# ISL6236A_PS.net
KiCad netlist of a schematic drawn in Altium Designer
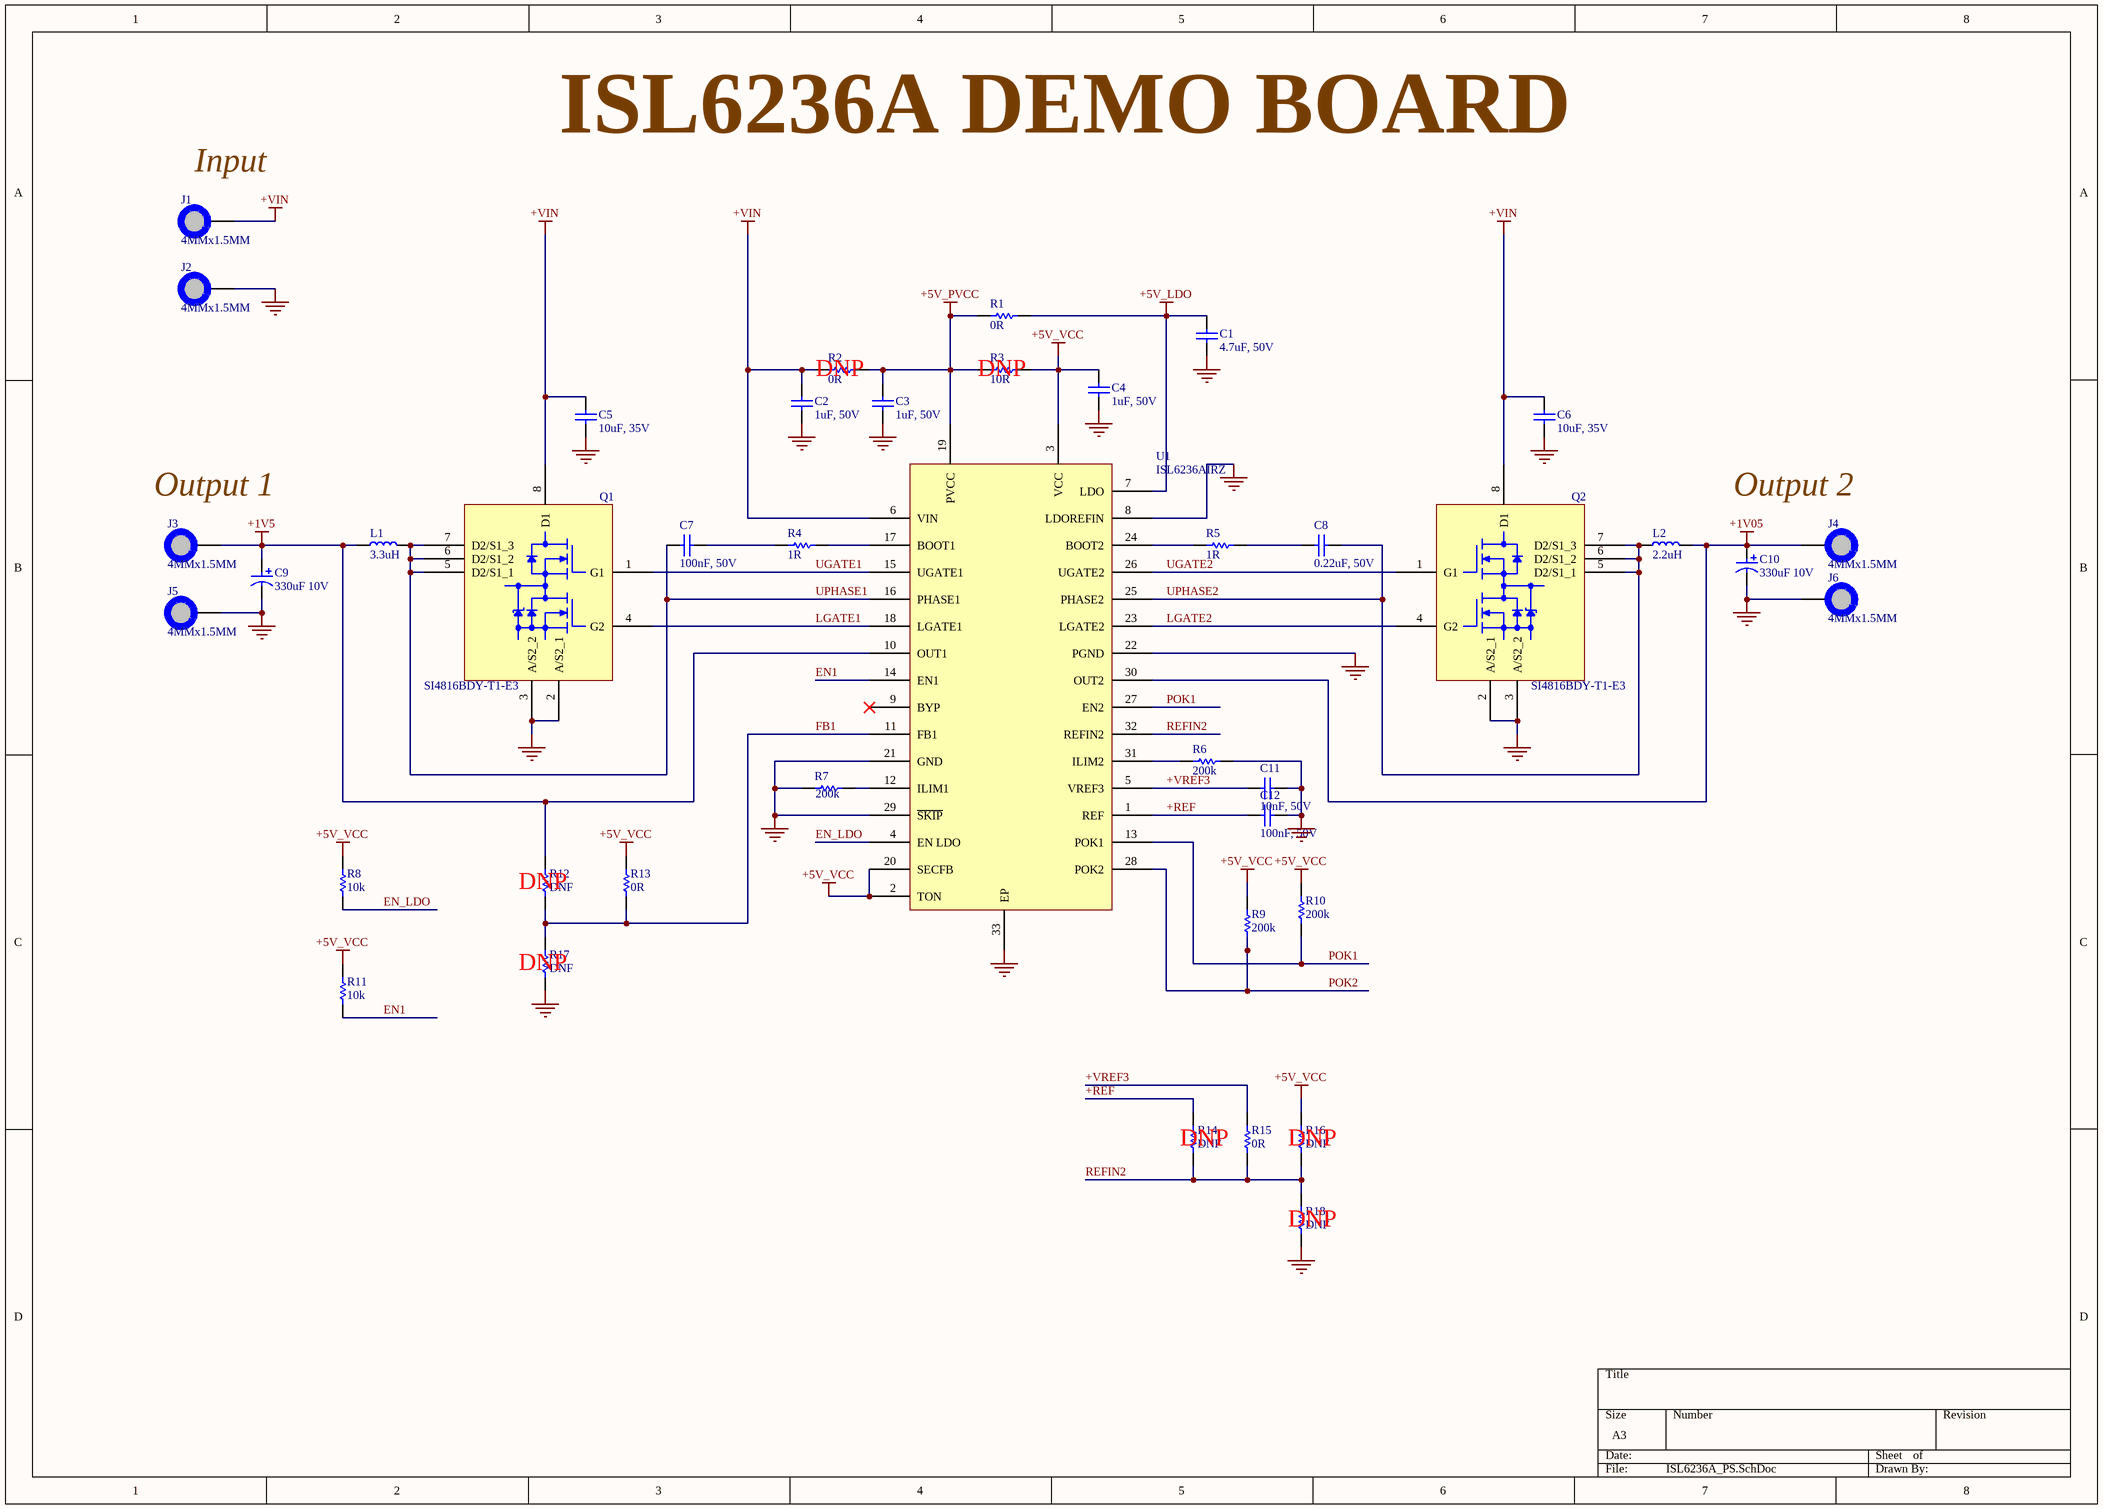
[diagram p0: ISL6236A_PS.SchDoc]

(export (version "E")
  (design (tool "Eeschema 10.0.6"))
  (components
    (comp (ref "C1")
      (value "4.7uF, 50V")
      (footprint "CAP1206")
      (description "CAP CER 4.7UF 50V X5R 1206")
      (fields
        (field (name "MANUFACTURER") "TDK")
        (field (name "MANUFACTURER PART NUMBER") "C3216X5R1H475K160AB")
      )
      (libsource (lib "ISL6236A_PS") (part "C3216X5R1H475K160AB"))
    )
    (comp (ref "C2")
      (value "1uF, 50V")
      (footprint "Cap0805")
      (description "CAP CER SMD/SMT 1uF 50 Volts 10% X7R")
      (fields
        (field (name "MANUFACTURER") "KEMET")
        (field (name "MANUFACTURER PART NUMBER") "C0805C105K5RACTU")
      )
      (libsource (lib "ISL6236A_PS") (part "C0805C105K5RACTU"))
    )
    (comp (ref "C3")
      (value "1uF, 50V")
      (footprint "Cap0805")
      (description "CAP CER SMD/SMT 1uF 50 Volts 10% X7R")
      (fields
        (field (name "MANUFACTURER") "KEMET")
        (field (name "MANUFACTURER PART NUMBER") "C0805C105K5RACTU")
      )
      (libsource (lib "ISL6236A_PS") (part "C0805C105K5RACTU"))
    )
    (comp (ref "C4")
      (value "1uF, 50V")
      (footprint "Cap0805")
      (description "CAP CER SMD/SMT 1uF 50 Volts 10% X7R")
      (fields
        (field (name "MANUFACTURER") "KEMET")
        (field (name "MANUFACTURER PART NUMBER") "C0805C105K5RACTU")
      )
      (libsource (lib "ISL6236A_PS") (part "C0805C105K5RACTU"))
    )
    (comp (ref "C5")
      (value "10uF, 35V")
      (footprint "CAP 1210")
      (description "CAP CER 10UF 35V X5R 1210")
      (fields
        (field (name "MANUFACTURER") "KEMET")
        (field (name "MANUFACTURER PART NUMBER") "C1210C106K6PACTU")
      )
      (libsource (lib "ISL6236A_PS") (part "C1210C106K6PACTU"))
    )
    (comp (ref "C6")
      (value "10uF, 35V")
      (footprint "CAP 1210")
      (description "CAP CER 10UF 35V X5R 1210")
      (fields
        (field (name "MANUFACTURER") "KEMET")
        (field (name "MANUFACTURER PART NUMBER") "C1210C106K6PACTU")
      )
      (libsource (lib "ISL6236A_PS") (part "C1210C106K6PACTU"))
    )
    (comp (ref "C7")
      (value "100nF, 50V")
      (footprint "Cap0805")
      (description "CAP CER 100nF; 50VDC; X7R; ±10%; SMD; 0805")
      (fields
        (field (name "MANUFACTURER") "KEMET")
        (field (name "MANUFACTURER PART NUMBER") "C0805C104K5RACTU")
      )
      (libsource (lib "ISL6236A_PS") (part "C0805C104K5RACTU"))
    )
    (comp (ref "C8")
      (value "0.22uF, 50V")
      (footprint "Cap0805")
      (description "CAP CER 0.22UF 50V X7R 0805")
      (fields
        (field (name "MANUFACTURER") "KEMET")
        (field (name "MANUFACTURER PART NUMBER") "C0805C224K5RACTU")
      )
      (libsource (lib "ISL6236A_PS") (part "C0805C224K5RACTU"))
    )
    (comp (ref "C9")
      (value "330uF 10V")
      (footprint "CAP 7343-43")
      (description "Tantalum Capacitors - Polymer SMD 330uF 10volts 20%")
      (fields
        (field (name "MANUFACTURER") "KEMET")
        (field (name "MANUFACTURER PART NUMBER") "T530X337M010ATE004")
      )
      (libsource (lib "ISL6236A_PS") (part "T530X337M010ATE004"))
    )
    (comp (ref "C10")
      (value "330uF 10V")
      (footprint "CAP 7343-43")
      (description "Tantalum Capacitors - Polymer SMD 330uF 10volts 20%")
      (fields
        (field (name "MANUFACTURER") "KEMET")
        (field (name "MANUFACTURER PART NUMBER") "T530X337M010ATE004")
      )
      (libsource (lib "ISL6236A_PS") (part "T530X337M010ATE004"))
    )
    (comp (ref "C11")
      (value "10nF, 50V")
      (footprint "Cap0805")
      (description "CAP CER 10000PF 50V X7R 0805")
      (fields
        (field (name "MANUFACTURER") "KEMET")
        (field (name "MANUFACTURER PART NUMBER") "C0805F103K5RACTU")
      )
      (libsource (lib "ISL6236A_PS") (part "C0805F103K5RACTU"))
    )
    (comp (ref "C12")
      (value "100nF, 50V")
      (footprint "Cap0805")
      (description "CAP CER 100nF; 50VDC; X7R; ±10%; SMD; 0805")
      (fields
        (field (name "MANUFACTURER") "KEMET")
        (field (name "MANUFACTURER PART NUMBER") "C0805C104K5RACTU")
      )
      (libsource (lib "ISL6236A_PS") (part "C0805C104K5RACTU"))
    )
    (comp (ref "J1")
      (value "4MMx1.5MM")
      (footprint "PAD_WITH_HOLE_4MMx1MM5")
      (description "PAd with a hole 4mm x 1.5mm")
      (libsource (lib "ISL6236A_PS") (part "PAD_WITH_HOLE_4MMx1MM5"))
    )
    (comp (ref "J2")
      (value "4MMx1.5MM")
      (footprint "PAD_WITH_HOLE_4MMx1MM5")
      (description "PAd with a hole 4mm x 1.5mm")
      (libsource (lib "ISL6236A_PS") (part "PAD_WITH_HOLE_4MMx1MM5"))
    )
    (comp (ref "J3")
      (value "4MMx1.5MM")
      (footprint "PAD_WITH_HOLE_4MMx1MM5")
      (description "PAd with a hole 4mm x 1.5mm")
      (libsource (lib "ISL6236A_PS") (part "PAD_WITH_HOLE_4MMx1MM5"))
    )
    (comp (ref "J4")
      (value "4MMx1.5MM")
      (footprint "PAD_WITH_HOLE_4MMx1MM5")
      (description "PAd with a hole 4mm x 1.5mm")
      (libsource (lib "ISL6236A_PS") (part "PAD_WITH_HOLE_4MMx1MM5"))
    )
    (comp (ref "J5")
      (value "4MMx1.5MM")
      (footprint "PAD_WITH_HOLE_4MMx1MM5")
      (description "PAd with a hole 4mm x 1.5mm")
      (libsource (lib "ISL6236A_PS") (part "PAD_WITH_HOLE_4MMx1MM5"))
    )
    (comp (ref "J6")
      (value "4MMx1.5MM")
      (footprint "PAD_WITH_HOLE_4MMx1MM5")
      (description "PAd with a hole 4mm x 1.5mm")
      (libsource (lib "ISL6236A_PS") (part "PAD_WITH_HOLE_4MMx1MM5"))
    )
    (comp (ref "L1")
      (value "3.3uH")
      (footprint "IND_DR125")
      (description "FIXED IND 3.3UH 12.7A 6.3 MOHM")
      (fields
        (field (name "MANUFACTURER") "Eaton Coiltronics")
        (field (name "MANUFACTURER PART NUMBER") "DR125-3R3-R")
      )
      (libsource (lib "ISL6236A_PS") (part "DR125-3R3-R"))
    )
    (comp (ref "L2")
      (value "2.2uH")
      (footprint "IND_DR125")
      (description "FIXED IND 2.2UH 10.9A 4.5 MOHM")
      (fields
        (field (name "MANUFACTURER") "Eaton Cooper")
        (field (name "MANUFACTURER PART NUMBER") "DR125-2R2-R")
      )
      (libsource (lib "ISL6236A_PS") (part "DR125-2R2-R"))
    )
    (comp (ref "Q1")
      (value "SI4816BDY-T1-E3")
      (footprint "SOP8")
      (description "MOSFET 2N-CH 30V 5.8A 8-SOIC")
      (fields (field (name "MANUFACTURER") "Vishay Siliconix"))
      (libsource (lib "ISL6236A_PS") (part "SI4816BDY-T1-E3"))
    )
    (comp (ref "Q2")
      (value "SI4816BDY-T1-E3")
      (footprint "SOP8")
      (description "MOSFET 2N-CH 30V 5.8A 8-SOIC")
      (fields (field (name "MANUFACTURER") "Vishay Siliconix"))
      (libsource (lib "") (part "SI4816BDY-T1-E3_1"))
    )
    (comp (ref "R1")
      (value "0R")
      (footprint "RES0805")
      (description "Thick Film Resistors - SMD 1/8W 0.0ohm 5%")
      (fields
        (field (name "MANUFACTURER") "Yageo")
        (field (name "MANUFACTURER PART NUMBER") "AC0805JR-070RL")
      )
      (libsource (lib "ISL6236A_PS") (part "AC0805JR-070RL"))
    )
    (comp (ref "R2")
      (value "0R")
      (footprint "RES0805")
      (description "Thick Film Resistors - SMD 1/8W 0.0ohm 5%")
      (fields
        (field (name "MANUFACTURER") "Yageo")
        (field (name "MANUFACTURER PART NUMBER") "AC0805JR-070RL")
      )
      (libsource (lib "ISL6236A_PS") (part "AC0805JR-070RL"))
    )
    (comp (ref "R3")
      (value "10R")
      (footprint "RES0805")
      (description "Thick Film Resistors - SMD 1/8W 10ohm 1% AEC-Q200")
      (fields
        (field (name "MANUFACTURER") "Yageo")
        (field (name "MANUFACTURER PART NUMBER") "AC0805FR-0710RL")
      )
      (libsource (lib "ISL6236A_PS") (part "AC0805FR-0710RL"))
    )
    (comp (ref "R4")
      (value "1R")
      (footprint "RES0805")
      (description "AC Series 0805 0.125 W 1 Ohm ±1% ±200 ppm/°C SMT Thick Film Chip Resistor")
      (fields
        (field (name "MANUFACTURER") "Yageo")
        (field (name "MANUFACTURER PART NUMBER") "AC0805FR-071RL")
      )
      (libsource (lib "ISL6236A_PS") (part "AC0805FR-071RL"))
    )
    (comp (ref "R5")
      (value "1R")
      (footprint "RES0805")
      (description "AC Series 0805 0.125 W 1 Ohm ±1% ±200 ppm/°C SMT Thick Film Chip Resistor")
      (fields
        (field (name "MANUFACTURER") "Yageo")
        (field (name "MANUFACTURER PART NUMBER") "AC0805FR-071RL")
      )
      (libsource (lib "ISL6236A_PS") (part "AC0805FR-071RL"))
    )
    (comp (ref "R6")
      (value "200k")
      (footprint "RES0805")
      (description "Thick Film Resistors - SMD 1/8W 200K ohm 1% AEC-Q200")
      (fields
        (field (name "MANUFACTURER") "Yageo")
        (field (name "MANUFACTURER PART NUMBER") "AC0805FR-07200KL")
      )
      (libsource (lib "ISL6236A_PS") (part "AC0805FR-07200KL"))
    )
    (comp (ref "R7")
      (value "200k")
      (footprint "RES0805")
      (description "Thick Film Resistors - SMD 1/8W 200K ohm 1% AEC-Q200")
      (fields
        (field (name "MANUFACTURER") "Yageo")
        (field (name "MANUFACTURER PART NUMBER") "AC0805FR-07200KL")
      )
      (libsource (lib "ISL6236A_PS") (part "AC0805FR-07200KL"))
    )
    (comp (ref "R8")
      (value "10k")
      (footprint "RES0805")
      (description "RES SMD 10K OHM 1% 1/8W 0805")
      (fields
        (field (name "MANUFACTURER") "Yageo")
        (field (name "MANUFACTURER PART NUMBER") "AC0805FR-0710KL")
      )
      (libsource (lib "ISL6236A_PS") (part "AC0805FR-0710KL"))
    )
    (comp (ref "R9")
      (value "200k")
      (footprint "RES0805")
      (description "Thick Film Resistors - SMD 1/8W 200K ohm 1% AEC-Q200")
      (fields
        (field (name "MANUFACTURER") "Yageo")
        (field (name "MANUFACTURER PART NUMBER") "AC0805FR-07200KL")
      )
      (libsource (lib "ISL6236A_PS") (part "AC0805FR-07200KL"))
    )
    (comp (ref "R10")
      (value "200k")
      (footprint "RES0805")
      (description "Thick Film Resistors - SMD 1/8W 200K ohm 1% AEC-Q200")
      (fields
        (field (name "MANUFACTURER") "Yageo")
        (field (name "MANUFACTURER PART NUMBER") "AC0805FR-07200KL")
      )
      (libsource (lib "ISL6236A_PS") (part "AC0805FR-07200KL"))
    )
    (comp (ref "R11")
      (value "10k")
      (footprint "RES0805")
      (description "RES SMD 10K OHM 1% 1/8W 0805")
      (fields
        (field (name "MANUFACTURER") "Yageo")
        (field (name "MANUFACTURER PART NUMBER") "AC0805FR-0710KL")
      )
      (libsource (lib "ISL6236A_PS") (part "AC0805FR-0710KL"))
    )
    (comp (ref "R12")
      (value "DNF")
      (footprint "RES0805")
      (description "RES General")
      (libsource (lib "ISL6236A_PS") (part "RES General"))
    )
    (comp (ref "R13")
      (value "0R")
      (footprint "RES0805")
      (description "Thick Film Resistors - SMD 1/8W 0.0ohm 5%")
      (fields
        (field (name "MANUFACTURER") "Yageo")
        (field (name "MANUFACTURER PART NUMBER") "AC0805JR-070RL")
      )
      (libsource (lib "ISL6236A_PS") (part "AC0805JR-070RL"))
    )
    (comp (ref "R14")
      (value "DNF")
      (footprint "RES0805")
      (description "RES General")
      (libsource (lib "ISL6236A_PS") (part "RES General"))
    )
    (comp (ref "R15")
      (value "0R")
      (footprint "RES0805")
      (description "Thick Film Resistors - SMD 1/8W 0.0ohm 5%")
      (fields
        (field (name "MANUFACTURER") "Yageo")
        (field (name "MANUFACTURER PART NUMBER") "AC0805JR-070RL")
      )
      (libsource (lib "ISL6236A_PS") (part "AC0805JR-070RL"))
    )
    (comp (ref "R16")
      (value "DNF")
      (footprint "RES0805")
      (description "RES General")
      (libsource (lib "ISL6236A_PS") (part "RES General"))
    )
    (comp (ref "R17")
      (value "DNF")
      (footprint "RES0805")
      (description "RES General")
      (libsource (lib "ISL6236A_PS") (part "RES General"))
    )
    (comp (ref "R18")
      (value "DNF")
      (footprint "RES0805")
      (description "RES General")
      (libsource (lib "ISL6236A_PS") (part "RES General"))
    )
    (comp (ref "U1")
      (value "ISL6236AIRZ")
      (footprint "L32.5x5B")
      (description "IC MAIN PWR CTRLR QUAD 32-QFN")
      (fields (field (name "MANUFACTURER") "Intersil"))
      (libsource (lib "ISL6236A_PS") (part "ISL6236AIRZ"))
    )
  )
  (nets
    (net (code "1") (name "+1V05") (class "Default")
      (node (ref "C10") (pin "1") (pinfunction "1_1") (pintype "passive"))
      (node (ref "J4") (pin "1") (pinfunction "1_1") (pintype "passive"))
      (node (ref "L2") (pin "2") (pinfunction "2_2") (pintype "passive"))
      (node (ref "U1") (pin "30") (pinfunction "OUT2_30") (pintype "passive"))
    )
    (net (code "2") (name "+1V5") (class "Default")
      (node (ref "C9") (pin "1") (pinfunction "1_1") (pintype "passive"))
      (node (ref "J3") (pin "1") (pinfunction "1_1") (pintype "passive"))
      (node (ref "L1") (pin "1") (pinfunction "1_1") (pintype "passive"))
      (node (ref "R12") (pin "2") (pinfunction "2_2") (pintype "passive"))
      (node (ref "U1") (pin "10") (pinfunction "OUT1_10") (pintype "passive"))
    )
    (net (code "3") (name "+5V_LDO") (class "Default")
      (node (ref "C1") (pin "2") (pinfunction "2_2") (pintype "passive"))
      (node (ref "R1") (pin "2") (pinfunction "2_2") (pintype "passive"))
      (node (ref "U1") (pin "7") (pinfunction "LDO_7") (pintype "passive"))
    )
    (net (code "4") (name "+5V_PVCC") (class "Default")
      (node (ref "C3") (pin "2") (pinfunction "2_2") (pintype "passive"))
      (node (ref "R1") (pin "1") (pinfunction "1_1") (pintype "passive"))
      (node (ref "R2") (pin "2") (pinfunction "2_2") (pintype "passive"))
      (node (ref "R3") (pin "1") (pinfunction "1_1") (pintype "passive"))
      (node (ref "U1") (pin "19") (pinfunction "PVCC_19") (pintype "passive"))
    )
    (net (code "5") (name "+5V_VCC") (class "Default")
      (node (ref "C4") (pin "2") (pinfunction "2_2") (pintype "passive"))
      (node (ref "R10") (pin "2") (pinfunction "2_2") (pintype "passive"))
      (node (ref "R11") (pin "2") (pinfunction "2_2") (pintype "passive"))
      (node (ref "R13") (pin "2") (pinfunction "2_2") (pintype "passive"))
      (node (ref "R16") (pin "2") (pinfunction "2_2") (pintype "passive"))
      (node (ref "R3") (pin "2") (pinfunction "2_2") (pintype "passive"))
      (node (ref "R8") (pin "2") (pinfunction "2_2") (pintype "passive"))
      (node (ref "R9") (pin "2") (pinfunction "2_2") (pintype "passive"))
      (node (ref "U1") (pin "2") (pinfunction "TON_2") (pintype "passive"))
      (node (ref "U1") (pin "20") (pinfunction "SECFB_20") (pintype "passive"))
      (node (ref "U1") (pin "3") (pinfunction "VCC_3") (pintype "passive"))
    )
    (net (code "6") (name "+VIN") (class "Default")
      (node (ref "C2") (pin "2") (pinfunction "2_2") (pintype "passive"))
      (node (ref "C5") (pin "2") (pinfunction "2_2") (pintype "passive"))
      (node (ref "C6") (pin "2") (pinfunction "2_2") (pintype "passive"))
      (node (ref "J1") (pin "1") (pinfunction "1_1") (pintype "passive"))
      (node (ref "Q1") (pin "8") (pinfunction "D1_8") (pintype "passive"))
      (node (ref "Q2") (pin "8") (pinfunction "D1_8") (pintype "passive"))
      (node (ref "R2") (pin "1") (pinfunction "1_1") (pintype "passive"))
      (node (ref "U1") (pin "6") (pinfunction "VIN_6") (pintype "passive"))
    )
    (net (code "7") (name "/+REF") (class "Default")
      (node (ref "C12") (pin "1") (pinfunction "1_1") (pintype "passive"))
      (node (ref "R14") (pin "2") (pinfunction "2_2") (pintype "passive"))
      (node (ref "U1") (pin "1") (pinfunction "REF_1") (pintype "passive"))
    )
    (net (code "8") (name "/+VREF3") (class "Default")
      (node (ref "C11") (pin "1") (pinfunction "1_1") (pintype "passive"))
      (node (ref "R15") (pin "2") (pinfunction "2_2") (pintype "passive"))
      (node (ref "U1") (pin "5") (pinfunction "VREF3_5") (pintype "passive"))
    )
    (net (code "9") (name "/EN1") (class "Default")
      (node (ref "R11") (pin "1") (pinfunction "1_1") (pintype "passive"))
      (node (ref "U1") (pin "14") (pinfunction "EN1_14") (pintype "passive"))
    )
    (net (code "10") (name "/EN_LDO") (class "Default")
      (node (ref "R8") (pin "1") (pinfunction "1_1") (pintype "passive"))
      (node (ref "U1") (pin "4") (pinfunction "EN_LDO_4") (pintype "passive"))
    )
    (net (code "11") (name "/FB1") (class "Default")
      (node (ref "R12") (pin "1") (pinfunction "1_1") (pintype "passive"))
      (node (ref "R13") (pin "1") (pinfunction "1_1") (pintype "passive"))
      (node (ref "R17") (pin "2") (pinfunction "2_2") (pintype "passive"))
      (node (ref "U1") (pin "11") (pinfunction "FB1_11") (pintype "passive"))
    )
    (net (code "12") (name "/LGATE1") (class "Default")
      (node (ref "Q1") (pin "4") (pinfunction "G2_4") (pintype "passive"))
      (node (ref "U1") (pin "18") (pinfunction "LGATE1_18") (pintype "passive"))
    )
    (net (code "13") (name "/LGATE2") (class "Default")
      (node (ref "Q2") (pin "4") (pinfunction "G2_4") (pintype "passive"))
      (node (ref "U1") (pin "23") (pinfunction "LGATE2_23") (pintype "passive"))
    )
    (net (code "14") (name "/POK1") (class "Default")
      (node (ref "R10") (pin "1") (pinfunction "1_1") (pintype "passive"))
      (node (ref "U1") (pin "13") (pinfunction "POK1_13") (pintype "passive"))
      (node (ref "U1") (pin "27") (pinfunction "EN2_27") (pintype "passive"))
    )
    (net (code "15") (name "/POK2") (class "Default")
      (node (ref "R9") (pin "1") (pinfunction "1_1") (pintype "passive"))
      (node (ref "U1") (pin "28") (pinfunction "POK2_28") (pintype "passive"))
    )
    (net (code "16") (name "/REFIN2") (class "Default")
      (node (ref "R14") (pin "1") (pinfunction "1_1") (pintype "passive"))
      (node (ref "R15") (pin "1") (pinfunction "1_1") (pintype "passive"))
      (node (ref "R16") (pin "1") (pinfunction "1_1") (pintype "passive"))
      (node (ref "R18") (pin "2") (pinfunction "2_2") (pintype "passive"))
      (node (ref "U1") (pin "32") (pinfunction "REFIN2_32") (pintype "passive"))
    )
    (net (code "17") (name "/UGATE1") (class "Default")
      (node (ref "Q1") (pin "1") (pinfunction "G1_1") (pintype "passive"))
      (node (ref "U1") (pin "15") (pinfunction "UGATE1_15") (pintype "passive"))
    )
    (net (code "18") (name "/UGATE2") (class "Default")
      (node (ref "Q2") (pin "1") (pinfunction "G1_1") (pintype "passive"))
      (node (ref "U1") (pin "26") (pinfunction "UGATE2_26") (pintype "passive"))
    )
    (net (code "19") (name "/UPHASE1") (class "Default")
      (node (ref "C7") (pin "1") (pinfunction "1_1") (pintype "passive"))
      (node (ref "L1") (pin "2") (pinfunction "2_2") (pintype "passive"))
      (node (ref "Q1") (pin "5") (pinfunction "D2/S1_1_5") (pintype "passive"))
      (node (ref "Q1") (pin "6") (pinfunction "D2/S1_2_6") (pintype "passive"))
      (node (ref "Q1") (pin "7") (pinfunction "D2/S1_3_7") (pintype "passive"))
      (node (ref "U1") (pin "16") (pinfunction "PHASE1_16") (pintype "passive"))
    )
    (net (code "20") (name "/UPHASE2") (class "Default")
      (node (ref "C8") (pin "2") (pinfunction "2_2") (pintype "passive"))
      (node (ref "L2") (pin "1") (pinfunction "1_1") (pintype "passive"))
      (node (ref "Q2") (pin "5") (pinfunction "D2/S1_1_5") (pintype "passive"))
      (node (ref "Q2") (pin "6") (pinfunction "D2/S1_2_6") (pintype "passive"))
      (node (ref "Q2") (pin "7") (pinfunction "D2/S1_3_7") (pintype "passive"))
      (node (ref "U1") (pin "25") (pinfunction "PHASE2_25") (pintype "passive"))
    )
    (net (code "21") (name "GND") (class "Default")
      (node (ref "C1") (pin "1") (pinfunction "1_1") (pintype "passive"))
      (node (ref "C10") (pin "2") (pinfunction "2_2") (pintype "passive"))
      (node (ref "C11") (pin "2") (pinfunction "2_2") (pintype "passive"))
      (node (ref "C12") (pin "2") (pinfunction "2_2") (pintype "passive"))
      (node (ref "C2") (pin "1") (pinfunction "1_1") (pintype "passive"))
      (node (ref "C3") (pin "1") (pinfunction "1_1") (pintype "passive"))
      (node (ref "C4") (pin "1") (pinfunction "1_1") (pintype "passive"))
      (node (ref "C5") (pin "1") (pinfunction "1_1") (pintype "passive"))
      (node (ref "C6") (pin "1") (pinfunction "1_1") (pintype "passive"))
      (node (ref "C9") (pin "2") (pinfunction "2_2") (pintype "passive"))
      (node (ref "J2") (pin "1") (pinfunction "1_1") (pintype "passive"))
      (node (ref "J5") (pin "1") (pinfunction "1_1") (pintype "passive"))
      (node (ref "J6") (pin "1") (pinfunction "1_1") (pintype "passive"))
      (node (ref "Q1") (pin "2") (pinfunction "A/S2_1_2") (pintype "passive"))
      (node (ref "Q1") (pin "3") (pinfunction "A/S2_2_3") (pintype "passive"))
      (node (ref "Q2") (pin "2") (pinfunction "A/S2_1_2") (pintype "passive"))
      (node (ref "Q2") (pin "3") (pinfunction "A/S2_2_3") (pintype "passive"))
      (node (ref "R17") (pin "1") (pinfunction "1_1") (pintype "passive"))
      (node (ref "R18") (pin "1") (pinfunction "1_1") (pintype "passive"))
      (node (ref "R6") (pin "2") (pinfunction "2_2") (pintype "passive"))
      (node (ref "R7") (pin "1") (pinfunction "1_1") (pintype "passive"))
      (node (ref "U1") (pin "21") (pinfunction "GND_21") (pintype "passive"))
      (node (ref "U1") (pin "22") (pinfunction "PGND_22") (pintype "passive"))
      (node (ref "U1") (pin "29") (pinfunction "~{SKIP}_29") (pintype "passive"))
      (node (ref "U1") (pin "33") (pinfunction "EP_33") (pintype "passive"))
      (node (ref "U1") (pin "8") (pinfunction "LDOREFIN_8") (pintype "passive"))
    )
    (net (code "22") (name "Net-(C7-Pad2)") (class "Default")
      (node (ref "C7") (pin "2") (pinfunction "2_2") (pintype "passive"))
      (node (ref "R4") (pin "1") (pinfunction "1_1") (pintype "passive"))
    )
    (net (code "23") (name "Net-(C8-Pad1)") (class "Default")
      (node (ref "C8") (pin "1") (pinfunction "1_1") (pintype "passive"))
      (node (ref "R5") (pin "2") (pinfunction "2_2") (pintype "passive"))
    )
    (net (code "24") (name "Net-(U1-BOOT1)") (class "Default")
      (node (ref "R4") (pin "2") (pinfunction "2_2") (pintype "passive"))
      (node (ref "U1") (pin "17") (pinfunction "BOOT1_17") (pintype "passive"))
    )
    (net (code "25") (name "Net-(U1-BOOT2)") (class "Default")
      (node (ref "R5") (pin "1") (pinfunction "1_1") (pintype "passive"))
      (node (ref "U1") (pin "24") (pinfunction "BOOT2_24") (pintype "passive"))
    )
    (net (code "26") (name "Net-(U1-ILIM1)") (class "Default")
      (node (ref "R7") (pin "2") (pinfunction "2_2") (pintype "passive"))
      (node (ref "U1") (pin "12") (pinfunction "ILIM1_12") (pintype "passive"))
    )
    (net (code "27") (name "Net-(U1-ILIM2)") (class "Default")
      (node (ref "R6") (pin "1") (pinfunction "1_1") (pintype "passive"))
      (node (ref "U1") (pin "31") (pinfunction "ILIM2_31") (pintype "passive"))
    )
    (net (code "28") (name "unconnected-(U1-BYP-Pad9)") (class "Default")
      (node (ref "U1") (pin "9") (pinfunction "BYP_9") (pintype "passive+no_connect"))
    )
  )
)
